# Sheet1.net
KiCad netlist of a schematic drawn in Altium Designer
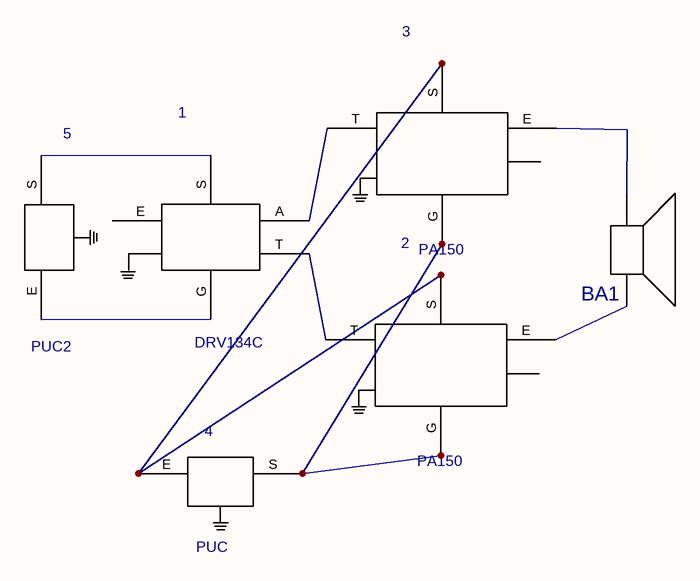
[diagram p0: Sheet1.SCHDOC]

(export (version "E")
  (design (tool "Eeschema 10.0.6"))
  (components
    (comp (ref "1") (value "DRV134C") (footprint "DRV134P") (libsource (lib "*") (part "DRV134C")))
    (comp (ref "2") (value "PA150") (footprint "PA150P") (libsource (lib "*") (part "PA150")))
    (comp (ref "3") (value "PA150") (footprint "PA150P") (libsource (lib "*") (part "PA150")))
    (comp (ref "4") (value "PUC") (footprint "PUP") (libsource (lib "*") (part "PUC")))
    (comp (ref "5") (value "PUC2") (footprint "PUP2") (libsource (lib "*") (part "PUC2")))
    (comp (ref "BA1") (value "0,25ГД-10") (footprint "0,25ГД-10") (libsource (lib "*") (part "0,25ГД-10")))
  )
  (nets
    (net (code "1") (name "Net-(1-PadA)") (class "Default")
      (node (ref "1") (pin "A") (pinfunction "A_A") (pintype "passive"))
      (node (ref "3") (pin "T") (pinfunction "T_T") (pintype "passive"))
    )
    (net (code "2") (name "Net-(1-PadG)") (class "Default")
      (node (ref "1") (pin "G") (pinfunction "G_G") (pintype "passive"))
      (node (ref "5") (pin "E") (pinfunction "E_E") (pintype "passive"))
    )
    (net (code "3") (name "Net-(1-PadS)") (class "Default")
      (node (ref "1") (pin "S") (pinfunction "S_S") (pintype "passive"))
      (node (ref "5") (pin "S") (pinfunction "S_S") (pintype "passive"))
    )
    (net (code "4") (name "Net-(1-PadT)") (class "Default")
      (node (ref "1") (pin "T") (pinfunction "T_T") (pintype "passive"))
      (node (ref "2") (pin "T") (pinfunction "T_T") (pintype "passive"))
    )
    (net (code "5") (name "Net-(2-PadE)") (class "Default")
      (node (ref "2") (pin "E") (pinfunction "E_E") (pintype "passive"))
      (node (ref "BA1") (pin "1") (pinfunction "1_1") (pintype "passive"))
    )
    (net (code "6") (name "Net-(2-PadG)") (class "Default")
      (node (ref "2") (pin "G") (pinfunction "G_G") (pintype "passive"))
      (node (ref "3") (pin "G") (pinfunction "G_G") (pintype "passive"))
      (node (ref "4") (pin "S") (pinfunction "S_S") (pintype "passive"))
    )
    (net (code "7") (name "Net-(2-PadS)") (class "Default")
      (node (ref "2") (pin "S") (pinfunction "S_S") (pintype "passive"))
      (node (ref "3") (pin "S") (pinfunction "S_S") (pintype "passive"))
      (node (ref "4") (pin "E") (pinfunction "E_E") (pintype "passive"))
    )
    (net (code "8") (name "Net-(3-PadE)") (class "Default")
      (node (ref "3") (pin "E") (pinfunction "E_E") (pintype "passive"))
      (node (ref "BA1") (pin "2") (pinfunction "2_2") (pintype "passive"))
    )
    (net (code "9") (name "unconnected-(1-PadE)") (class "Default")
      (node (ref "1") (pin "E") (pinfunction "E_E") (pintype "passive"))
    )
    (net (code "10") (name "unconnected-(BA1-Pad3)") (class "Default")
      (node (ref "BA1") (pin "3") (pintype "passive"))
    )
    (net (code "11") (name "unconnected-(BA1-Pad4)") (class "Default")
      (node (ref "BA1") (pin "4") (pintype "passive"))
    )
    (net (code "12") (name "unconnected-(BA1-Pad5)") (class "Default")
      (node (ref "BA1") (pin "5") (pintype "passive"))
    )
    (net (code "13") (name "unconnected-(BA1-Pad6)") (class "Default")
      (node (ref "BA1") (pin "6") (pintype "passive"))
    )
  )
)
